# relay.net
KiCad netlist of a schematic drawn in Altium Designer
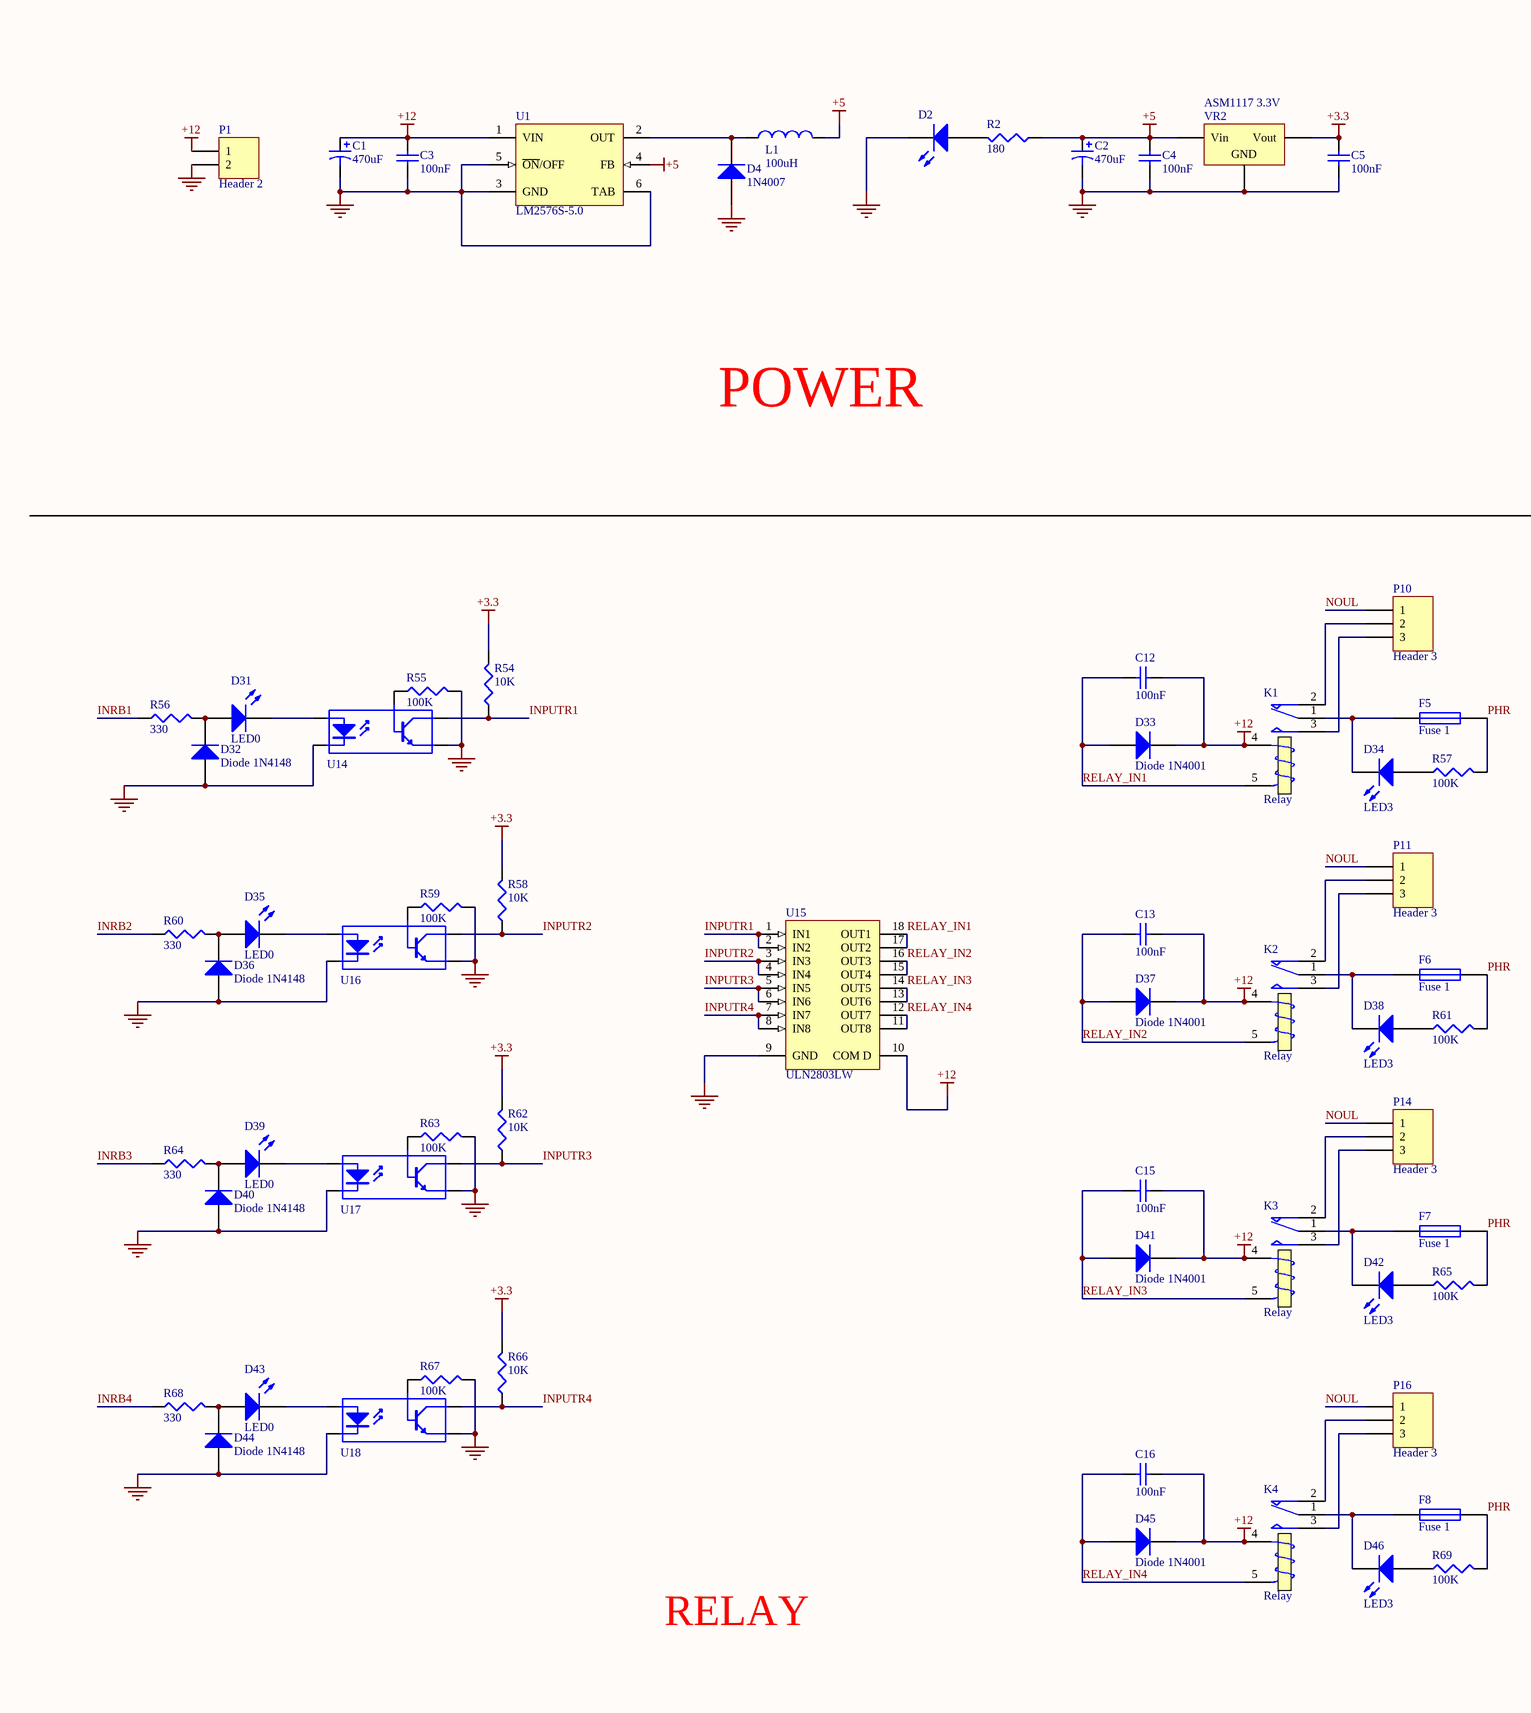
[diagram p0: relay.SchDoc, left]
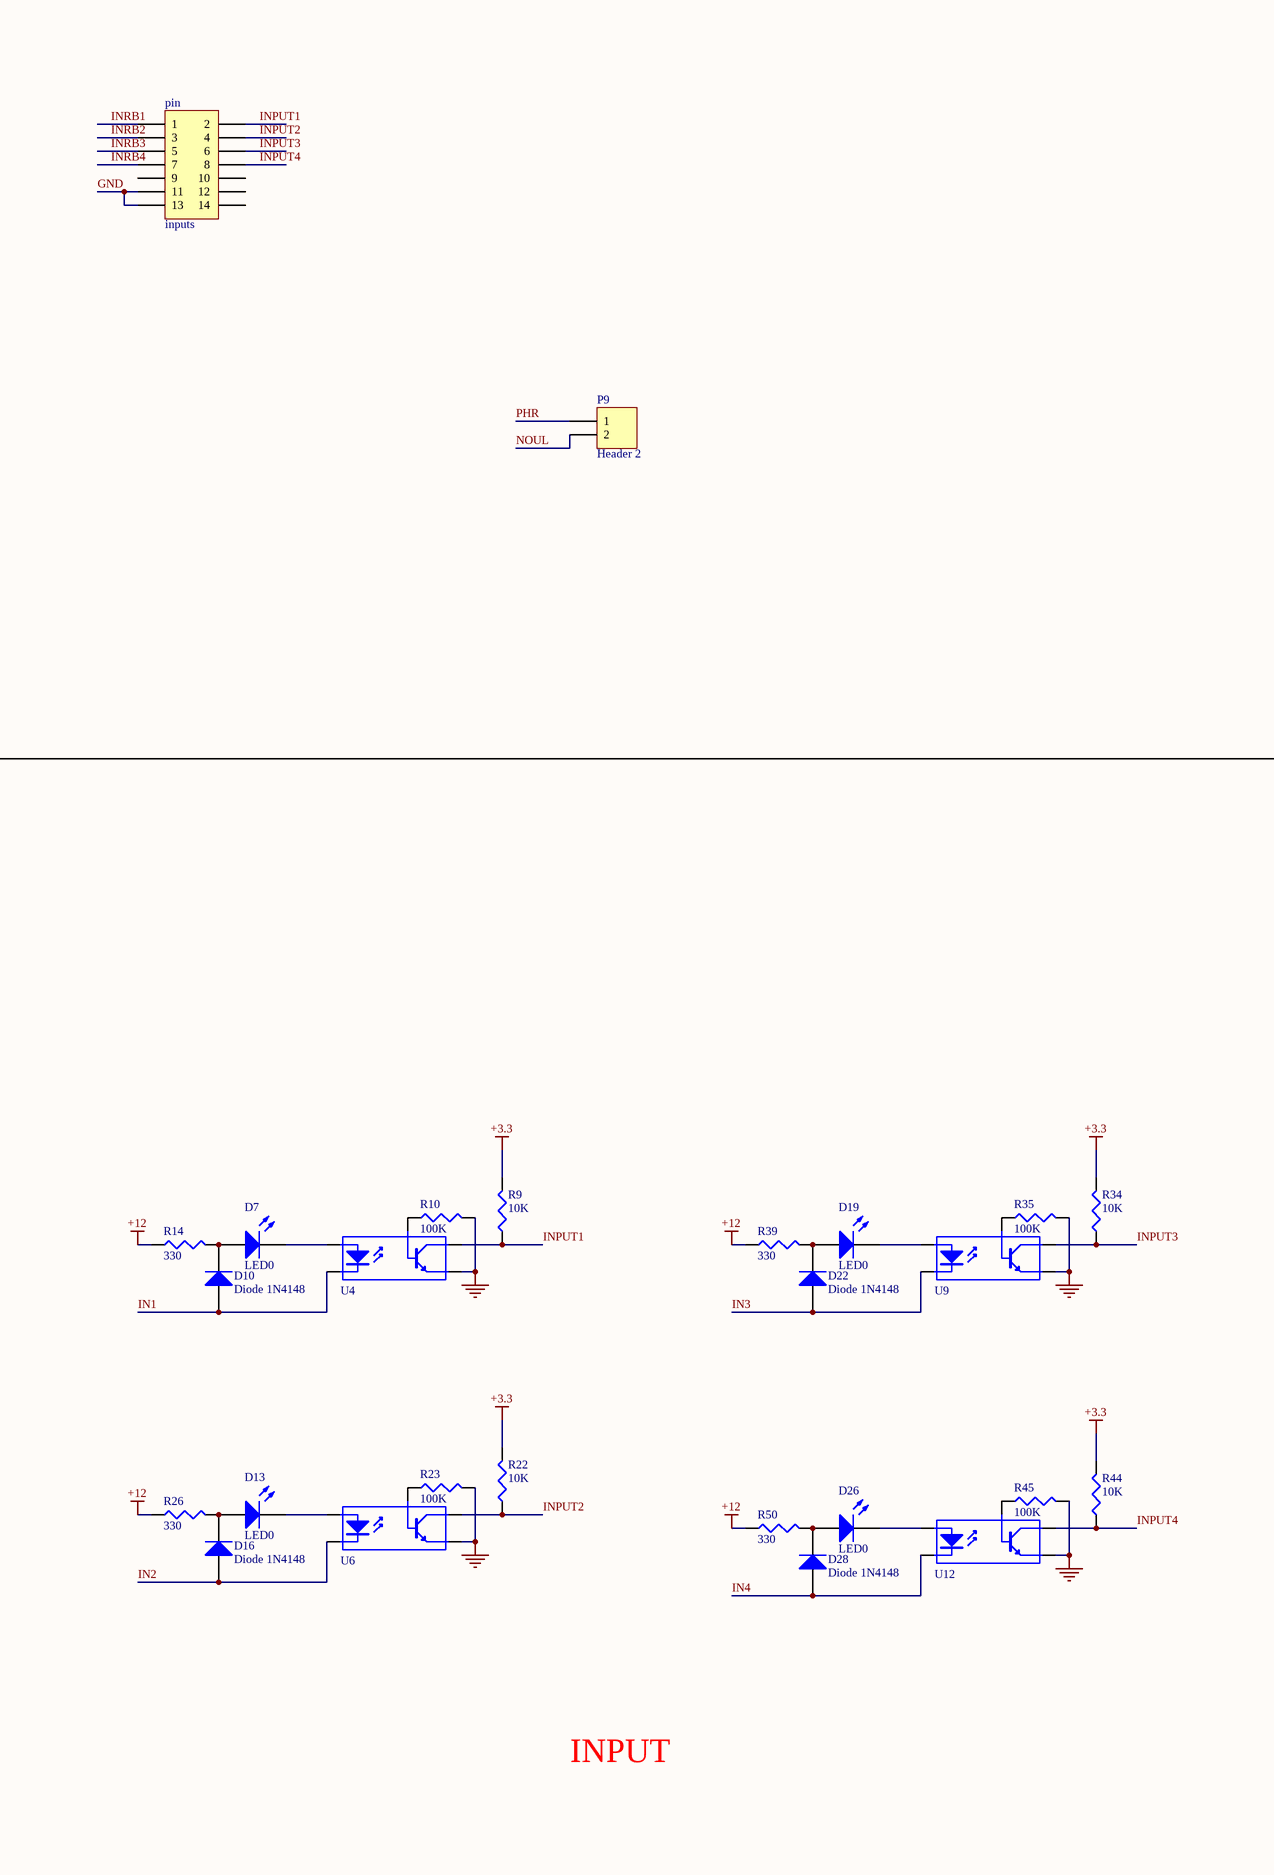
[diagram p1: relay.SchDoc, right]

(export (version "E")
  (design (tool "Eeschema 10.0.6"))
  (components
    (comp (ref "C1")
      (value "470uF")
      (footprint "CAP470")
      (description "Polarized Capacitor (Radial)")
      (fields (field (name "PUBLISHER") "Altium Limited"))
      (libsource (lib "*") (part "Cap Pol1"))
    )
    (comp (ref "C2")
      (value "470uF")
      (footprint "CAP470")
      (description "Polarized Capacitor (Radial)")
      (fields (field (name "PUBLISHER") "Altium Limited"))
      (libsource (lib "*") (part "Cap Pol1"))
    )
    (comp (ref "C3")
      (value "100nF")
      (footprint "1206")
      (description "Capacitor (Semiconductor SIM Model)")
      (fields (field (name "PUBLISHER") "Altium Limited"))
      (libsource (lib "*") (part "Cap Semi"))
    )
    (comp (ref "C4")
      (value "100nF")
      (footprint "1206")
      (description "Capacitor (Semiconductor SIM Model)")
      (fields (field (name "PUBLISHER") "Altium Limited"))
      (libsource (lib "*") (part "Cap Semi"))
    )
    (comp (ref "C5")
      (value "100nF")
      (footprint "1206")
      (description "Capacitor (Semiconductor SIM Model)")
      (fields (field (name "PUBLISHER") "Altium Limited"))
      (libsource (lib "*") (part "Cap Semi"))
    )
    (comp (ref "C12")
      (value "100nF")
      (footprint "1206")
      (description "Capacitor (Semiconductor SIM Model)")
      (fields (field (name "PUBLISHER") "Altium Limited"))
      (libsource (lib "*") (part "Cap Semi"))
    )
    (comp (ref "C13")
      (value "100nF")
      (footprint "1206")
      (description "Capacitor (Semiconductor SIM Model)")
      (fields (field (name "PUBLISHER") "Altium Limited"))
      (libsource (lib "*") (part "Cap Semi"))
    )
    (comp (ref "C15")
      (value "100nF")
      (footprint "1206")
      (description "Capacitor (Semiconductor SIM Model)")
      (fields (field (name "PUBLISHER") "Altium Limited"))
      (libsource (lib "*") (part "Cap Semi"))
    )
    (comp (ref "C16")
      (value "100nF")
      (footprint "1206")
      (description "Capacitor (Semiconductor SIM Model)")
      (fields (field (name "PUBLISHER") "Altium Limited"))
      (libsource (lib "*") (part "Cap Semi"))
    )
    (comp (ref "D2")
      (value "LED RED")
      (footprint "LED-1206")
      (description "Typical INFRARED GaAs LED")
      (fields (field (name "PUBLISHER") "Altium Limited"))
      (libsource (lib "*") (part "LED0"))
    )
    (comp (ref "D4")
      (value "1N4007")
      (footprint "1N4007")
      (description "1 Amp General Purpose Rectifier")
      (fields (field (name "PUBLISHER") "Altium Limited"))
      (libsource (lib "*") (part "Diode 1N4007"))
    )
    (comp (ref "D7")
      (value "LED0")
      (footprint "LED-1206")
      (description "Typical INFRARED GaAs LED")
      (fields (field (name "PUBLISHER") "Altium Limited"))
      (libsource (lib "*") (part "LED0"))
    )
    (comp (ref "D10")
      (value "Diode 1N4148")
      (footprint "Diode")
      (description "High Conductance Fast Diode")
      (fields (field (name "PUBLISHER") "Altium Limited"))
      (libsource (lib "*") (part "Diode 1N4148"))
    )
    (comp (ref "D13")
      (value "LED0")
      (footprint "LED-1206")
      (description "Typical INFRARED GaAs LED")
      (fields (field (name "PUBLISHER") "Altium Limited"))
      (libsource (lib "*") (part "LED0"))
    )
    (comp (ref "D16")
      (value "Diode 1N4148")
      (footprint "Diode")
      (description "High Conductance Fast Diode")
      (fields (field (name "PUBLISHER") "Altium Limited"))
      (libsource (lib "*") (part "Diode 1N4148"))
    )
    (comp (ref "D19")
      (value "LED0")
      (footprint "LED-1206")
      (description "Typical INFRARED GaAs LED")
      (fields (field (name "PUBLISHER") "Altium Limited"))
      (libsource (lib "*") (part "LED0"))
    )
    (comp (ref "D22")
      (value "Diode 1N4148")
      (footprint "Diode")
      (description "High Conductance Fast Diode")
      (fields (field (name "PUBLISHER") "Altium Limited"))
      (libsource (lib "*") (part "Diode 1N4148"))
    )
    (comp (ref "D26")
      (value "LED0")
      (footprint "LED-1206")
      (description "Typical INFRARED GaAs LED")
      (fields (field (name "PUBLISHER") "Altium Limited"))
      (libsource (lib "*") (part "LED0"))
    )
    (comp (ref "D28")
      (value "Diode 1N4148")
      (footprint "Diode")
      (description "High Conductance Fast Diode")
      (fields (field (name "PUBLISHER") "Altium Limited"))
      (libsource (lib "*") (part "Diode 1N4148"))
    )
    (comp (ref "D31")
      (value "LED0")
      (footprint "LED-1206")
      (description "Typical INFRARED GaAs LED")
      (fields (field (name "PUBLISHER") "Altium Limited"))
      (libsource (lib "*") (part "LED0"))
    )
    (comp (ref "D32")
      (value "Diode 1N4148")
      (footprint "Diode")
      (description "High Conductance Fast Diode")
      (fields (field (name "PUBLISHER") "Altium Limited"))
      (libsource (lib "*") (part "Diode 1N4148"))
    )
    (comp (ref "D33")
      (value "Diode 1N4001")
      (footprint "1N4007")
      (description "1 Amp General Purpose Rectifier")
      (fields (field (name "PUBLISHER") "Altium Limited"))
      (libsource (lib "*") (part "Diode 1N4001"))
    )
    (comp (ref "D34")
      (value "LED3")
      (footprint "LED-1206")
      (description "Typical BLUE SiC LED")
      (fields (field (name "PUBLISHER") "Altium Limited"))
      (libsource (lib "*") (part "LED3"))
    )
    (comp (ref "D35")
      (value "LED0")
      (footprint "LED-1206")
      (description "Typical INFRARED GaAs LED")
      (fields (field (name "PUBLISHER") "Altium Limited"))
      (libsource (lib "*") (part "LED0"))
    )
    (comp (ref "D36")
      (value "Diode 1N4148")
      (footprint "Diode")
      (description "High Conductance Fast Diode")
      (fields (field (name "PUBLISHER") "Altium Limited"))
      (libsource (lib "*") (part "Diode 1N4148"))
    )
    (comp (ref "D37")
      (value "Diode 1N4001")
      (footprint "1N4007")
      (description "1 Amp General Purpose Rectifier")
      (fields (field (name "PUBLISHER") "Altium Limited"))
      (libsource (lib "*") (part "Diode 1N4001"))
    )
    (comp (ref "D38")
      (value "LED3")
      (footprint "LED-1206")
      (description "Typical BLUE SiC LED")
      (fields (field (name "PUBLISHER") "Altium Limited"))
      (libsource (lib "*") (part "LED3"))
    )
    (comp (ref "D39")
      (value "LED0")
      (footprint "LED-1206")
      (description "Typical INFRARED GaAs LED")
      (fields (field (name "PUBLISHER") "Altium Limited"))
      (libsource (lib "*") (part "LED0"))
    )
    (comp (ref "D40")
      (value "Diode 1N4148")
      (footprint "Diode")
      (description "High Conductance Fast Diode")
      (fields (field (name "PUBLISHER") "Altium Limited"))
      (libsource (lib "*") (part "Diode 1N4148"))
    )
    (comp (ref "D41")
      (value "Diode 1N4001")
      (footprint "1N4007")
      (description "1 Amp General Purpose Rectifier")
      (fields (field (name "PUBLISHER") "Altium Limited"))
      (libsource (lib "*") (part "Diode 1N4001"))
    )
    (comp (ref "D42")
      (value "LED3")
      (footprint "LED-1206")
      (description "Typical BLUE SiC LED")
      (fields (field (name "PUBLISHER") "Altium Limited"))
      (libsource (lib "*") (part "LED3"))
    )
    (comp (ref "D43")
      (value "LED0")
      (footprint "LED-1206")
      (description "Typical INFRARED GaAs LED")
      (fields (field (name "PUBLISHER") "Altium Limited"))
      (libsource (lib "*") (part "LED0"))
    )
    (comp (ref "D44")
      (value "Diode 1N4148")
      (footprint "Diode")
      (description "High Conductance Fast Diode")
      (fields (field (name "PUBLISHER") "Altium Limited"))
      (libsource (lib "*") (part "Diode 1N4148"))
    )
    (comp (ref "D45")
      (value "Diode 1N4001")
      (footprint "1N4007")
      (description "1 Amp General Purpose Rectifier")
      (fields (field (name "PUBLISHER") "Altium Limited"))
      (libsource (lib "*") (part "Diode 1N4001"))
    )
    (comp (ref "D46")
      (value "LED3")
      (footprint "LED-1206")
      (description "Typical BLUE SiC LED")
      (fields (field (name "PUBLISHER") "Altium Limited"))
      (libsource (lib "*") (part "LED3"))
    )
    (comp (ref "F5")
      (value "Fuse 1")
      (footprint "FUSEXX")
      (description "Fuse")
      (fields (field (name "PUBLISHER") "Altium Limited"))
      (libsource (lib "*") (part "Fuse 1"))
    )
    (comp (ref "F6")
      (value "Fuse 1")
      (footprint "FUSEXX")
      (description "Fuse")
      (fields (field (name "PUBLISHER") "Altium Limited"))
      (libsource (lib "*") (part "Fuse 1"))
    )
    (comp (ref "F7")
      (value "Fuse 1")
      (footprint "FUSEXX")
      (description "Fuse")
      (fields (field (name "PUBLISHER") "Altium Limited"))
      (libsource (lib "*") (part "Fuse 1"))
    )
    (comp (ref "F8")
      (value "Fuse 1")
      (footprint "FUSEXX")
      (description "Fuse")
      (fields (field (name "PUBLISHER") "Altium Limited"))
      (libsource (lib "*") (part "Fuse 1"))
    )
    (comp (ref "K1")
      (value "Relay")
      (footprint "RELEY")
      (description "SPDT Relay")
      (fields (field (name "PUBLISHER") "Altium Limited"))
      (libsource (lib "*") (part "Relay"))
    )
    (comp (ref "K2")
      (value "Relay")
      (footprint "RELEY")
      (description "SPDT Relay")
      (fields (field (name "PUBLISHER") "Altium Limited"))
      (libsource (lib "*") (part "Relay"))
    )
    (comp (ref "K3")
      (value "Relay")
      (footprint "RELEY")
      (description "SPDT Relay")
      (fields (field (name "PUBLISHER") "Altium Limited"))
      (libsource (lib "*") (part "Relay"))
    )
    (comp (ref "K4")
      (value "Relay")
      (footprint "RELEY")
      (description "SPDT Relay")
      (fields (field (name "PUBLISHER") "Altium Limited"))
      (libsource (lib "*") (part "Relay"))
    )
    (comp (ref "L1") (value "100uH") (footprint "L-.2/.4") (libsource (lib "*") (part "INDUCTOR")))
    (comp (ref "P1")
      (value "Header 2")
      (footprint "POWER2_NEW")
      (description "Header, 2-Pin")
      (fields (field (name "PUBLISHER") "Altium Limited"))
      (libsource (lib "*") (part "Header 2"))
    )
    (comp (ref "P9")
      (value "Header 2")
      (footprint "POWER2_NEW")
      (description "Header, 2-Pin")
      (fields (field (name "PUBLISHER") "Altium Limited"))
      (libsource (lib "*") (part "Header 2"))
    )
    (comp (ref "P10")
      (value "Header 3")
      (footprint "POWER3_NEW")
      (description "Header, 3-Pin")
      (fields (field (name "PUBLISHER") "Altium Limited"))
      (libsource (lib "*") (part "Header 3"))
    )
    (comp (ref "P11")
      (value "Header 3")
      (footprint "POWER3_NEW")
      (description "Header, 3-Pin")
      (fields (field (name "PUBLISHER") "Altium Limited"))
      (libsource (lib "*") (part "Header 3"))
    )
    (comp (ref "P14")
      (value "Header 3")
      (footprint "POWER3_NEW")
      (description "Header, 3-Pin")
      (fields (field (name "PUBLISHER") "Altium Limited"))
      (libsource (lib "*") (part "Header 3"))
    )
    (comp (ref "P16")
      (value "Header 3")
      (footprint "POWER3_NEW")
      (description "Header, 3-Pin")
      (fields (field (name "PUBLISHER") "Altium Limited"))
      (libsource (lib "*") (part "Header 3"))
    )
    (comp (ref "pin")
      (value "inputs")
      (footprint "HDR2X7")
      (description "Header, 7-Pin, Dual row")
      (fields (field (name "PUBLISHER") "Altium Limited"))
      (libsource (lib "Miscellaneous Connectors") (part "Header 7X2"))
    )
    (comp (ref "R2")
      (value "180")
      (footprint "1206")
      (description "Resistor")
      (fields (field (name "Comment") "180R") (field (name "PUBLISHER") "Altium Limited"))
      (libsource (lib "*") (part "Res3"))
    )
    (comp (ref "R9")
      (value "10K")
      (footprint "1206")
      (description "Resistor")
      (fields (field (name "PUBLISHER") "Altium Limited"))
      (libsource (lib "*") (part "Res3"))
    )
    (comp (ref "R10")
      (value "100K")
      (footprint "1206")
      (description "Resistor")
      (fields (field (name "PUBLISHER") "Altium Limited"))
      (libsource (lib "*") (part "Res3"))
    )
    (comp (ref "R14")
      (value "330")
      (footprint "1206")
      (description "Resistor")
      (fields (field (name "PUBLISHER") "Altium Limited"))
      (libsource (lib "*") (part "Res3"))
    )
    (comp (ref "R22")
      (value "10K")
      (footprint "1206")
      (description "Resistor")
      (fields (field (name "PUBLISHER") "Altium Limited"))
      (libsource (lib "*") (part "Res3"))
    )
    (comp (ref "R23")
      (value "100K")
      (footprint "1206")
      (description "Resistor")
      (fields (field (name "PUBLISHER") "Altium Limited"))
      (libsource (lib "*") (part "Res3"))
    )
    (comp (ref "R26")
      (value "330")
      (footprint "1206")
      (description "Resistor")
      (fields (field (name "PUBLISHER") "Altium Limited"))
      (libsource (lib "*") (part "Res3"))
    )
    (comp (ref "R34")
      (value "10K")
      (footprint "1206")
      (description "Resistor")
      (fields (field (name "PUBLISHER") "Altium Limited"))
      (libsource (lib "*") (part "Res3"))
    )
    (comp (ref "R35")
      (value "100K")
      (footprint "1206")
      (description "Resistor")
      (fields (field (name "PUBLISHER") "Altium Limited"))
      (libsource (lib "*") (part "Res3"))
    )
    (comp (ref "R39")
      (value "330")
      (footprint "1206")
      (description "Resistor")
      (fields (field (name "PUBLISHER") "Altium Limited"))
      (libsource (lib "*") (part "Res3"))
    )
    (comp (ref "R44")
      (value "10K")
      (footprint "1206")
      (description "Resistor")
      (fields (field (name "PUBLISHER") "Altium Limited"))
      (libsource (lib "*") (part "Res3"))
    )
    (comp (ref "R45")
      (value "100K")
      (footprint "1206")
      (description "Resistor")
      (fields (field (name "PUBLISHER") "Altium Limited"))
      (libsource (lib "*") (part "Res3"))
    )
    (comp (ref "R50")
      (value "330")
      (footprint "1206")
      (description "Resistor")
      (fields (field (name "PUBLISHER") "Altium Limited"))
      (libsource (lib "*") (part "Res3"))
    )
    (comp (ref "R54")
      (value "10K")
      (footprint "1206")
      (description "Resistor")
      (fields (field (name "PUBLISHER") "Altium Limited"))
      (libsource (lib "*") (part "Res3"))
    )
    (comp (ref "R55")
      (value "100K")
      (footprint "1206")
      (description "Resistor")
      (fields (field (name "PUBLISHER") "Altium Limited"))
      (libsource (lib "*") (part "Res3"))
    )
    (comp (ref "R56")
      (value "330")
      (footprint "1206")
      (description "Resistor")
      (fields (field (name "PUBLISHER") "Altium Limited"))
      (libsource (lib "*") (part "Res3"))
    )
    (comp (ref "R57")
      (value "100K")
      (footprint "1206")
      (description "Resistor")
      (fields (field (name "PUBLISHER") "Altium Limited"))
      (libsource (lib "*") (part "Res3"))
    )
    (comp (ref "R58")
      (value "10K")
      (footprint "1206")
      (description "Resistor")
      (fields (field (name "PUBLISHER") "Altium Limited"))
      (libsource (lib "*") (part "Res3"))
    )
    (comp (ref "R59")
      (value "100K")
      (footprint "1206")
      (description "Resistor")
      (fields (field (name "PUBLISHER") "Altium Limited"))
      (libsource (lib "*") (part "Res3"))
    )
    (comp (ref "R60")
      (value "330")
      (footprint "1206")
      (description "Resistor")
      (fields (field (name "PUBLISHER") "Altium Limited"))
      (libsource (lib "*") (part "Res3"))
    )
    (comp (ref "R61")
      (value "100K")
      (footprint "1206")
      (description "Resistor")
      (fields (field (name "PUBLISHER") "Altium Limited"))
      (libsource (lib "*") (part "Res3"))
    )
    (comp (ref "R62")
      (value "10K")
      (footprint "1206")
      (description "Resistor")
      (fields (field (name "PUBLISHER") "Altium Limited"))
      (libsource (lib "*") (part "Res3"))
    )
    (comp (ref "R63")
      (value "100K")
      (footprint "1206")
      (description "Resistor")
      (fields (field (name "PUBLISHER") "Altium Limited"))
      (libsource (lib "*") (part "Res3"))
    )
    (comp (ref "R64")
      (value "330")
      (footprint "1206")
      (description "Resistor")
      (fields (field (name "PUBLISHER") "Altium Limited"))
      (libsource (lib "*") (part "Res3"))
    )
    (comp (ref "R65")
      (value "100K")
      (footprint "1206")
      (description "Resistor")
      (fields (field (name "PUBLISHER") "Altium Limited"))
      (libsource (lib "*") (part "Res3"))
    )
    (comp (ref "R66")
      (value "10K")
      (footprint "1206")
      (description "Resistor")
      (fields (field (name "PUBLISHER") "Altium Limited"))
      (libsource (lib "*") (part "Res3"))
    )
    (comp (ref "R67")
      (value "100K")
      (footprint "1206")
      (description "Resistor")
      (fields (field (name "PUBLISHER") "Altium Limited"))
      (libsource (lib "*") (part "Res3"))
    )
    (comp (ref "R68")
      (value "330")
      (footprint "1206")
      (description "Resistor")
      (fields (field (name "PUBLISHER") "Altium Limited"))
      (libsource (lib "*") (part "Res3"))
    )
    (comp (ref "R69")
      (value "100K")
      (footprint "1206")
      (description "Resistor")
      (fields (field (name "PUBLISHER") "Altium Limited"))
      (libsource (lib "*") (part "Res3"))
    )
    (comp (ref "U1")
      (value "LM2576S-5.0")
      (footprint "TS5B_N")
      (description "SIMPLE SWITCHER; 3A Step-Down Voltage Regulator")
      (fields
        (field (name "MANUFACTURER") "National Semiconductor")
        (field (name "DIGIKEYPARTNUMBER") "LM2576S-5.0-ND")
        (field (name "PUBLISHER") "Altium Limited")
      )
      (libsource (lib "*") (part "LM2576S-5.0"))
    )
    (comp (ref "U4")
      (value "4N29")
      (footprint "Opto")
      (description "5 Pin Mini Flat Pack Optocoupler")
      (fields (field (name "PUBLISHER") "Altium Limited"))
      (libsource (lib "*") (part "4N29"))
    )
    (comp (ref "U6")
      (value "4N29")
      (footprint "Opto")
      (description "5 Pin Mini Flat Pack Optocoupler")
      (fields (field (name "PUBLISHER") "Altium Limited"))
      (libsource (lib "*") (part "4N29"))
    )
    (comp (ref "U9")
      (value "4N29")
      (footprint "Opto")
      (description "5 Pin Mini Flat Pack Optocoupler")
      (fields (field (name "PUBLISHER") "Altium Limited"))
      (libsource (lib "*") (part "4N29"))
    )
    (comp (ref "U12")
      (value "4N29")
      (footprint "Opto")
      (description "5 Pin Mini Flat Pack Optocoupler")
      (fields (field (name "PUBLISHER") "Altium Limited"))
      (libsource (lib "*") (part "4N29"))
    )
    (comp (ref "U14")
      (value "4N29")
      (footprint "Opto")
      (description "5 Pin Mini Flat Pack Optocoupler")
      (fields (field (name "PUBLISHER") "Altium Limited"))
      (libsource (lib "*") (part "4N29"))
    )
    (comp (ref "U15")
      (value "ULN2803LW")
      (footprint "LW18_N")
      (description "High-Voltage, High-Current Darlington Array")
      (fields (field (name "PUBLISHER") "Altium Limited"))
      (libsource (lib "*") (part "ULN2803LW"))
    )
    (comp (ref "U16")
      (value "4N29")
      (footprint "Opto")
      (description "5 Pin Mini Flat Pack Optocoupler")
      (fields (field (name "PUBLISHER") "Altium Limited"))
      (libsource (lib "*") (part "4N29"))
    )
    (comp (ref "U17")
      (value "4N29")
      (footprint "Opto")
      (description "5 Pin Mini Flat Pack Optocoupler")
      (fields (field (name "PUBLISHER") "Altium Limited"))
      (libsource (lib "*") (part "4N29"))
    )
    (comp (ref "U18")
      (value "4N29")
      (footprint "Opto")
      (description "5 Pin Mini Flat Pack Optocoupler")
      (fields (field (name "PUBLISHER") "Altium Limited"))
      (libsource (lib "*") (part "4N29"))
    )
    (comp (ref "VR2")
      (value "ASM1117 3.3V")
      (footprint "Regolator")
      (description "Voltage Regulator")
      (fields (field (name "PUBLISHER") "Altium Limited"))
      (libsource (lib "*") (part "Volt Reg_1"))
    )
  )
  (nets
    (net (code "1") (name "+3.3") (class "Default")
      (node (ref "C5") (pin "2") (pinfunction "2_2") (pintype "passive"))
      (node (ref "R22") (pin "2") (pinfunction "2_2") (pintype "passive"))
      (node (ref "R34") (pin "2") (pinfunction "2_2") (pintype "passive"))
      (node (ref "R44") (pin "2") (pinfunction "2_2") (pintype "passive"))
      (node (ref "R54") (pin "2") (pinfunction "2_2") (pintype "passive"))
      (node (ref "R58") (pin "2") (pinfunction "2_2") (pintype "passive"))
      (node (ref "R62") (pin "2") (pinfunction "2_2") (pintype "passive"))
      (node (ref "R66") (pin "2") (pinfunction "2_2") (pintype "passive"))
      (node (ref "R9") (pin "2") (pinfunction "2_2") (pintype "passive"))
      (node (ref "VR2") (pin "4") (pinfunction "Vout_4") (pintype "passive"))
    )
    (net (code "2") (name "+5") (class "Default")
      (node (ref "C2") (pin "1") (pinfunction "1_1") (pintype "passive"))
      (node (ref "C4") (pin "2") (pinfunction "2_2") (pintype "passive"))
      (node (ref "L1") (pin "2") (pinfunction "2_2") (pintype "passive"))
      (node (ref "R2") (pin "1") (pinfunction "1_1") (pintype "passive"))
      (node (ref "U1") (pin "4") (pinfunction "FB_4") (pintype "input"))
      (node (ref "VR2") (pin "3") (pinfunction "Vin_3") (pintype "passive"))
    )
    (net (code "3") (name "+12") (class "Default")
      (node (ref "C1") (pin "1") (pinfunction "1_1") (pintype "passive"))
      (node (ref "C12") (pin "2") (pinfunction "2_2") (pintype "passive"))
      (node (ref "C13") (pin "2") (pinfunction "2_2") (pintype "passive"))
      (node (ref "C15") (pin "2") (pinfunction "2_2") (pintype "passive"))
      (node (ref "C16") (pin "2") (pinfunction "2_2") (pintype "passive"))
      (node (ref "C3") (pin "2") (pinfunction "2_2") (pintype "passive"))
      (node (ref "D33") (pin "2") (pinfunction "K_2") (pintype "passive"))
      (node (ref "D37") (pin "2") (pinfunction "K_2") (pintype "passive"))
      (node (ref "D41") (pin "2") (pinfunction "K_2") (pintype "passive"))
      (node (ref "D45") (pin "2") (pinfunction "K_2") (pintype "passive"))
      (node (ref "K1") (pin "4") (pinfunction "T1_4") (pintype "passive"))
      (node (ref "K2") (pin "4") (pinfunction "T1_4") (pintype "passive"))
      (node (ref "K3") (pin "4") (pinfunction "T1_4") (pintype "passive"))
      (node (ref "K4") (pin "4") (pinfunction "T1_4") (pintype "passive"))
      (node (ref "P1") (pin "1") (pinfunction "1_1") (pintype "passive"))
      (node (ref "R14") (pin "1") (pinfunction "1_1") (pintype "passive"))
      (node (ref "R26") (pin "1") (pinfunction "1_1") (pintype "passive"))
      (node (ref "R39") (pin "1") (pinfunction "1_1") (pintype "passive"))
      (node (ref "R50") (pin "1") (pinfunction "1_1") (pintype "passive"))
      (node (ref "U1") (pin "1") (pinfunction "VIN_1") (pintype "power_in"))
      (node (ref "U15") (pin "10") (pinfunction "COM_D_10") (pintype "passive"))
    )
    (net (code "4") (name "/IN1") (class "Default")
      (node (ref "D10") (pin "1") (pinfunction "A_1") (pintype "passive"))
      (node (ref "U4") (pin "3") (pinfunction "K_3") (pintype "passive"))
    )
    (net (code "5") (name "/IN2") (class "Default")
      (node (ref "D16") (pin "1") (pinfunction "A_1") (pintype "passive"))
      (node (ref "U6") (pin "3") (pinfunction "K_3") (pintype "passive"))
    )
    (net (code "6") (name "/IN3") (class "Default")
      (node (ref "D22") (pin "1") (pinfunction "A_1") (pintype "passive"))
      (node (ref "U9") (pin "3") (pinfunction "K_3") (pintype "passive"))
    )
    (net (code "7") (name "/IN4") (class "Default")
      (node (ref "D28") (pin "1") (pinfunction "A_1") (pintype "passive"))
      (node (ref "U12") (pin "3") (pinfunction "K_3") (pintype "passive"))
    )
    (net (code "8") (name "/INPUT1") (class "Default")
      (node (ref "R9") (pin "1") (pinfunction "1_1") (pintype "passive"))
      (node (ref "U4") (pin "5") (pinfunction "C_5") (pintype "passive"))
      (node (ref "pin") (pin "2") (pinfunction "2_2") (pintype "passive"))
    )
    (net (code "9") (name "/INPUT2") (class "Default")
      (node (ref "R22") (pin "1") (pinfunction "1_1") (pintype "passive"))
      (node (ref "U6") (pin "5") (pinfunction "C_5") (pintype "passive"))
      (node (ref "pin") (pin "4") (pinfunction "4_4") (pintype "passive"))
    )
    (net (code "10") (name "/INPUT3") (class "Default")
      (node (ref "R34") (pin "1") (pinfunction "1_1") (pintype "passive"))
      (node (ref "U9") (pin "5") (pinfunction "C_5") (pintype "passive"))
      (node (ref "pin") (pin "6") (pinfunction "6_6") (pintype "passive"))
    )
    (net (code "11") (name "/INPUT4") (class "Default")
      (node (ref "R44") (pin "1") (pinfunction "1_1") (pintype "passive"))
      (node (ref "U12") (pin "5") (pinfunction "C_5") (pintype "passive"))
      (node (ref "pin") (pin "8") (pinfunction "8_8") (pintype "passive"))
    )
    (net (code "12") (name "/INPUTR1") (class "Default")
      (node (ref "R54") (pin "1") (pinfunction "1_1") (pintype "passive"))
      (node (ref "U14") (pin "5") (pinfunction "C_5") (pintype "passive"))
      (node (ref "U15") (pin "1") (pinfunction "IN1_1") (pintype "input"))
      (node (ref "U15") (pin "2") (pinfunction "IN2_2") (pintype "input"))
    )
    (net (code "13") (name "/INPUTR2") (class "Default")
      (node (ref "R58") (pin "1") (pinfunction "1_1") (pintype "passive"))
      (node (ref "U15") (pin "3") (pinfunction "IN3_3") (pintype "input"))
      (node (ref "U15") (pin "4") (pinfunction "IN4_4") (pintype "input"))
      (node (ref "U16") (pin "5") (pinfunction "C_5") (pintype "passive"))
    )
    (net (code "14") (name "/INPUTR3") (class "Default")
      (node (ref "R62") (pin "1") (pinfunction "1_1") (pintype "passive"))
      (node (ref "U15") (pin "5") (pinfunction "IN5_5") (pintype "input"))
      (node (ref "U15") (pin "6") (pinfunction "IN6_6") (pintype "input"))
      (node (ref "U17") (pin "5") (pinfunction "C_5") (pintype "passive"))
    )
    (net (code "15") (name "/INPUTR4") (class "Default")
      (node (ref "R66") (pin "1") (pinfunction "1_1") (pintype "passive"))
      (node (ref "U15") (pin "7") (pinfunction "IN7_7") (pintype "input"))
      (node (ref "U15") (pin "8") (pinfunction "IN8_8") (pintype "input"))
      (node (ref "U18") (pin "5") (pinfunction "C_5") (pintype "passive"))
    )
    (net (code "16") (name "/INRB1") (class "Default")
      (node (ref "R56") (pin "1") (pinfunction "1_1") (pintype "passive"))
      (node (ref "pin") (pin "1") (pinfunction "1_1") (pintype "passive"))
    )
    (net (code "17") (name "/INRB2") (class "Default")
      (node (ref "R60") (pin "1") (pinfunction "1_1") (pintype "passive"))
      (node (ref "pin") (pin "3") (pinfunction "3_3") (pintype "passive"))
    )
    (net (code "18") (name "/INRB3") (class "Default")
      (node (ref "R64") (pin "1") (pinfunction "1_1") (pintype "passive"))
      (node (ref "pin") (pin "5") (pinfunction "5_5") (pintype "passive"))
    )
    (net (code "19") (name "/INRB4") (class "Default")
      (node (ref "R68") (pin "1") (pinfunction "1_1") (pintype "passive"))
      (node (ref "pin") (pin "7") (pinfunction "7_7") (pintype "passive"))
    )
    (net (code "20") (name "/NOUL") (class "Default")
      (node (ref "P10") (pin "1") (pinfunction "1_1") (pintype "passive"))
      (node (ref "P11") (pin "1") (pinfunction "1_1") (pintype "passive"))
      (node (ref "P14") (pin "1") (pinfunction "1_1") (pintype "passive"))
      (node (ref "P16") (pin "1") (pinfunction "1_1") (pintype "passive"))
      (node (ref "P9") (pin "2") (pinfunction "2_2") (pintype "passive"))
    )
    (net (code "21") (name "/PHR") (class "Default")
      (node (ref "F5") (pin "2") (pinfunction "2_2") (pintype "passive"))
      (node (ref "F6") (pin "2") (pinfunction "2_2") (pintype "passive"))
      (node (ref "F7") (pin "2") (pinfunction "2_2") (pintype "passive"))
      (node (ref "F8") (pin "2") (pinfunction "2_2") (pintype "passive"))
      (node (ref "P9") (pin "1") (pinfunction "1_1") (pintype "passive"))
      (node (ref "R57") (pin "2") (pinfunction "2_2") (pintype "passive"))
      (node (ref "R61") (pin "2") (pinfunction "2_2") (pintype "passive"))
      (node (ref "R65") (pin "2") (pinfunction "2_2") (pintype "passive"))
      (node (ref "R69") (pin "2") (pinfunction "2_2") (pintype "passive"))
    )
    (net (code "22") (name "/RELAY_IN1") (class "Default")
      (node (ref "C12") (pin "1") (pinfunction "1_1") (pintype "passive"))
      (node (ref "D33") (pin "1") (pinfunction "A_1") (pintype "passive"))
      (node (ref "K1") (pin "5") (pinfunction "T2_5") (pintype "passive"))
      (node (ref "U15") (pin "17") (pinfunction "OUT2_17") (pintype "open_collector"))
      (node (ref "U15") (pin "18") (pinfunction "OUT1_18") (pintype "open_collector"))
    )
    (net (code "23") (name "/RELAY_IN2") (class "Default")
      (node (ref "C13") (pin "1") (pinfunction "1_1") (pintype "passive"))
      (node (ref "D37") (pin "1") (pinfunction "A_1") (pintype "passive"))
      (node (ref "K2") (pin "5") (pinfunction "T2_5") (pintype "passive"))
      (node (ref "U15") (pin "15") (pinfunction "OUT4_15") (pintype "open_collector"))
      (node (ref "U15") (pin "16") (pinfunction "OUT3_16") (pintype "open_collector"))
    )
    (net (code "24") (name "/RELAY_IN3") (class "Default")
      (node (ref "C15") (pin "1") (pinfunction "1_1") (pintype "passive"))
      (node (ref "D41") (pin "1") (pinfunction "A_1") (pintype "passive"))
      (node (ref "K3") (pin "5") (pinfunction "T2_5") (pintype "passive"))
      (node (ref "U15") (pin "13") (pinfunction "OUT6_13") (pintype "open_collector"))
      (node (ref "U15") (pin "14") (pinfunction "OUT5_14") (pintype "open_collector"))
    )
    (net (code "25") (name "/RELAY_IN4") (class "Default")
      (node (ref "C16") (pin "1") (pinfunction "1_1") (pintype "passive"))
      (node (ref "D45") (pin "1") (pinfunction "A_1") (pintype "passive"))
      (node (ref "K4") (pin "5") (pinfunction "T2_5") (pintype "passive"))
      (node (ref "U15") (pin "11") (pinfunction "OUT8_11") (pintype "open_collector"))
      (node (ref "U15") (pin "12") (pinfunction "OUT7_12") (pintype "open_collector"))
    )
    (net (code "26") (name "GND") (class "Default")
      (node (ref "C1") (pin "2") (pinfunction "2_2") (pintype "passive"))
      (node (ref "C2") (pin "2") (pinfunction "2_2") (pintype "passive"))
      (node (ref "C3") (pin "1") (pinfunction "1_1") (pintype "passive"))
      (node (ref "C4") (pin "1") (pinfunction "1_1") (pintype "passive"))
      (node (ref "C5") (pin "1") (pinfunction "1_1") (pintype "passive"))
      (node (ref "D2") (pin "2") (pinfunction "K_2") (pintype "passive"))
      (node (ref "D32") (pin "1") (pinfunction "A_1") (pintype "passive"))
      (node (ref "D36") (pin "1") (pinfunction "A_1") (pintype "passive"))
      (node (ref "D4") (pin "1") (pinfunction "A_1") (pintype "passive"))
      (node (ref "D40") (pin "1") (pinfunction "A_1") (pintype "passive"))
      (node (ref "D44") (pin "1") (pinfunction "A_1") (pintype "passive"))
      (node (ref "P1") (pin "2") (pinfunction "2_2") (pintype "passive"))
      (node (ref "R10") (pin "2") (pinfunction "2_2") (pintype "passive"))
      (node (ref "R23") (pin "2") (pinfunction "2_2") (pintype "passive"))
      (node (ref "R35") (pin "2") (pinfunction "2_2") (pintype "passive"))
      (node (ref "R45") (pin "2") (pinfunction "2_2") (pintype "passive"))
      (node (ref "R55") (pin "2") (pinfunction "2_2") (pintype "passive"))
      (node (ref "R59") (pin "2") (pinfunction "2_2") (pintype "passive"))
      (node (ref "R63") (pin "2") (pinfunction "2_2") (pintype "passive"))
      (node (ref "R67") (pin "2") (pinfunction "2_2") (pintype "passive"))
      (node (ref "U1") (pin "3") (pinfunction "GND_3") (pintype "power_in"))
      (node (ref "U1") (pin "5") (pinfunction "~{ON}/OFF_5") (pintype "input"))
      (node (ref "U1") (pin "6") (pinfunction "TAB_6") (pintype "power_in"))
      (node (ref "U12") (pin "4") (pinfunction "E_4") (pintype "passive"))
      (node (ref "U14") (pin "3") (pinfunction "K_3") (pintype "passive"))
      (node (ref "U14") (pin "4") (pinfunction "E_4") (pintype "passive"))
      (node (ref "U15") (pin "9") (pinfunction "GND_9") (pintype "power_in"))
      (node (ref "U16") (pin "3") (pinfunction "K_3") (pintype "passive"))
      (node (ref "U16") (pin "4") (pinfunction "E_4") (pintype "passive"))
      (node (ref "U17") (pin "3") (pinfunction "K_3") (pintype "passive"))
      (node (ref "U17") (pin "4") (pinfunction "E_4") (pintype "passive"))
      (node (ref "U18") (pin "3") (pinfunction "K_3") (pintype "passive"))
      (node (ref "U18") (pin "4") (pinfunction "E_4") (pintype "passive"))
      (node (ref "U4") (pin "4") (pinfunction "E_4") (pintype "passive"))
      (node (ref "U6") (pin "4") (pinfunction "E_4") (pintype "passive"))
      (node (ref "U9") (pin "4") (pinfunction "E_4") (pintype "passive"))
      (node (ref "VR2") (pin "1") (pinfunction "GND_1") (pintype "passive"))
      (node (ref "pin") (pin "11") (pinfunction "11_11") (pintype "passive"))
      (node (ref "pin") (pin "13") (pinfunction "13_13") (pintype "passive"))
    )
    (net (code "27") (name "Net-(D2-A)") (class "Default")
      (node (ref "D2") (pin "1") (pinfunction "A_1") (pintype "passive"))
      (node (ref "R2") (pin "2") (pinfunction "2_2") (pintype "passive"))
    )
    (net (code "28") (name "Net-(D4-K)") (class "Default")
      (node (ref "D4") (pin "2") (pinfunction "K_2") (pintype "passive"))
      (node (ref "L1") (pin "1") (pinfunction "1_1") (pintype "passive"))
      (node (ref "U1") (pin "2") (pinfunction "OUT_2") (pintype "power_in"))
    )
    (net (code "29") (name "Net-(D7-K)") (class "Default")
      (node (ref "D7") (pin "2") (pinfunction "K_2") (pintype "passive"))
      (node (ref "U4") (pin "1") (pinfunction "A_1") (pintype "passive"))
    )
    (net (code "30") (name "Net-(D10-K)") (class "Default")
      (node (ref "D10") (pin "2") (pinfunction "K_2") (pintype "passive"))
      (node (ref "D7") (pin "1") (pinfunction "A_1") (pintype "passive"))
      (node (ref "R14") (pin "2") (pinfunction "2_2") (pintype "passive"))
    )
    (net (code "31") (name "Net-(D13-A)") (class "Default")
      (node (ref "D13") (pin "1") (pinfunction "A_1") (pintype "passive"))
      (node (ref "D16") (pin "2") (pinfunction "K_2") (pintype "passive"))
      (node (ref "R26") (pin "2") (pinfunction "2_2") (pintype "passive"))
    )
    (net (code "32") (name "Net-(D13-K)") (class "Default")
      (node (ref "D13") (pin "2") (pinfunction "K_2") (pintype "passive"))
      (node (ref "U6") (pin "1") (pinfunction "A_1") (pintype "passive"))
    )
    (net (code "33") (name "Net-(D19-A)") (class "Default")
      (node (ref "D19") (pin "1") (pinfunction "A_1") (pintype "passive"))
      (node (ref "D22") (pin "2") (pinfunction "K_2") (pintype "passive"))
      (node (ref "R39") (pin "2") (pinfunction "2_2") (pintype "passive"))
    )
    (net (code "34") (name "Net-(D19-K)") (class "Default")
      (node (ref "D19") (pin "2") (pinfunction "K_2") (pintype "passive"))
      (node (ref "U9") (pin "1") (pinfunction "A_1") (pintype "passive"))
    )
    (net (code "35") (name "Net-(D26-A)") (class "Default")
      (node (ref "D26") (pin "1") (pinfunction "A_1") (pintype "passive"))
      (node (ref "D28") (pin "2") (pinfunction "K_2") (pintype "passive"))
      (node (ref "R50") (pin "2") (pinfunction "2_2") (pintype "passive"))
    )
    (net (code "36") (name "Net-(D26-K)") (class "Default")
      (node (ref "D26") (pin "2") (pinfunction "K_2") (pintype "passive"))
      (node (ref "U12") (pin "1") (pinfunction "A_1") (pintype "passive"))
    )
    (net (code "37") (name "Net-(D31-A)") (class "Default")
      (node (ref "D31") (pin "1") (pinfunction "A_1") (pintype "passive"))
      (node (ref "D32") (pin "2") (pinfunction "K_2") (pintype "passive"))
      (node (ref "R56") (pin "2") (pinfunction "2_2") (pintype "passive"))
    )
    (net (code "38") (name "Net-(D31-K)") (class "Default")
      (node (ref "D31") (pin "2") (pinfunction "K_2") (pintype "passive"))
      (node (ref "U14") (pin "1") (pinfunction "A_1") (pintype "passive"))
    )
    (net (code "39") (name "Net-(D34-A)") (class "Default")
      (node (ref "D34") (pin "1") (pinfunction "A_1") (pintype "passive"))
      (node (ref "R57") (pin "1") (pinfunction "1_1") (pintype "passive"))
    )
    (net (code "40") (name "Net-(D34-K)") (class "Default")
      (node (ref "D34") (pin "2") (pinfunction "K_2") (pintype "passive"))
      (node (ref "F5") (pin "1") (pinfunction "1_1") (pintype "passive"))
      (node (ref "K1") (pin "1") (pinfunction "COM_1") (pintype "passive"))
    )
    (net (code "41") (name "Net-(D35-A)") (class "Default")
      (node (ref "D35") (pin "1") (pinfunction "A_1") (pintype "passive"))
      (node (ref "D36") (pin "2") (pinfunction "K_2") (pintype "passive"))
      (node (ref "R60") (pin "2") (pinfunction "2_2") (pintype "passive"))
    )
    (net (code "42") (name "Net-(D35-K)") (class "Default")
      (node (ref "D35") (pin "2") (pinfunction "K_2") (pintype "passive"))
      (node (ref "U16") (pin "1") (pinfunction "A_1") (pintype "passive"))
    )
    (net (code "43") (name "Net-(D38-A)") (class "Default")
      (node (ref "D38") (pin "1") (pinfunction "A_1") (pintype "passive"))
      (node (ref "R61") (pin "1") (pinfunction "1_1") (pintype "passive"))
    )
    (net (code "44") (name "Net-(D38-K)") (class "Default")
      (node (ref "D38") (pin "2") (pinfunction "K_2") (pintype "passive"))
      (node (ref "F6") (pin "1") (pinfunction "1_1") (pintype "passive"))
      (node (ref "K2") (pin "1") (pinfunction "COM_1") (pintype "passive"))
    )
    (net (code "45") (name "Net-(D39-A)") (class "Default")
      (node (ref "D39") (pin "1") (pinfunction "A_1") (pintype "passive"))
      (node (ref "D40") (pin "2") (pinfunction "K_2") (pintype "passive"))
      (node (ref "R64") (pin "2") (pinfunction "2_2") (pintype "passive"))
    )
    (net (code "46") (name "Net-(D39-K)") (class "Default")
      (node (ref "D39") (pin "2") (pinfunction "K_2") (pintype "passive"))
      (node (ref "U17") (pin "1") (pinfunction "A_1") (pintype "passive"))
    )
    (net (code "47") (name "Net-(D42-A)") (class "Default")
      (node (ref "D42") (pin "1") (pinfunction "A_1") (pintype "passive"))
      (node (ref "R65") (pin "1") (pinfunction "1_1") (pintype "passive"))
    )
    (net (code "48") (name "Net-(D42-K)") (class "Default")
      (node (ref "D42") (pin "2") (pinfunction "K_2") (pintype "passive"))
      (node (ref "F7") (pin "1") (pinfunction "1_1") (pintype "passive"))
      (node (ref "K3") (pin "1") (pinfunction "COM_1") (pintype "passive"))
    )
    (net (code "49") (name "Net-(D43-A)") (class "Default")
      (node (ref "D43") (pin "1") (pinfunction "A_1") (pintype "passive"))
      (node (ref "D44") (pin "2") (pinfunction "K_2") (pintype "passive"))
      (node (ref "R68") (pin "2") (pinfunction "2_2") (pintype "passive"))
    )
    (net (code "50") (name "Net-(D43-K)") (class "Default")
      (node (ref "D43") (pin "2") (pinfunction "K_2") (pintype "passive"))
      (node (ref "U18") (pin "1") (pinfunction "A_1") (pintype "passive"))
    )
    (net (code "51") (name "Net-(D46-A)") (class "Default")
      (node (ref "D46") (pin "1") (pinfunction "A_1") (pintype "passive"))
      (node (ref "R69") (pin "1") (pinfunction "1_1") (pintype "passive"))
    )
    (net (code "52") (name "Net-(D46-K)") (class "Default")
      (node (ref "D46") (pin "2") (pinfunction "K_2") (pintype "passive"))
      (node (ref "F8") (pin "1") (pinfunction "1_1") (pintype "passive"))
      (node (ref "K4") (pin "1") (pinfunction "COM_1") (pintype "passive"))
    )
    (net (code "53") (name "Net-(K1-NC)") (class "Default")
      (node (ref "K1") (pin "2") (pinfunction "NC_2") (pintype "passive"))
      (node (ref "P10") (pin "2") (pinfunction "2_2") (pintype "passive"))
    )
    (net (code "54") (name "Net-(K1-NO)") (class "Default")
      (node (ref "K1") (pin "3") (pinfunction "NO_3") (pintype "passive"))
      (node (ref "P10") (pin "3") (pinfunction "3_3") (pintype "passive"))
    )
    (net (code "55") (name "Net-(K2-NC)") (class "Default")
      (node (ref "K2") (pin "2") (pinfunction "NC_2") (pintype "passive"))
      (node (ref "P11") (pin "2") (pinfunction "2_2") (pintype "passive"))
    )
    (net (code "56") (name "Net-(K2-NO)") (class "Default")
      (node (ref "K2") (pin "3") (pinfunction "NO_3") (pintype "passive"))
      (node (ref "P11") (pin "3") (pinfunction "3_3") (pintype "passive"))
    )
    (net (code "57") (name "Net-(K3-NC)") (class "Default")
      (node (ref "K3") (pin "2") (pinfunction "NC_2") (pintype "passive"))
      (node (ref "P14") (pin "2") (pinfunction "2_2") (pintype "passive"))
    )
    (net (code "58") (name "Net-(K3-NO)") (class "Default")
      (node (ref "K3") (pin "3") (pinfunction "NO_3") (pintype "passive"))
      (node (ref "P14") (pin "3") (pinfunction "3_3") (pintype "passive"))
    )
    (net (code "59") (name "Net-(K4-NC)") (class "Default")
      (node (ref "K4") (pin "2") (pinfunction "NC_2") (pintype "passive"))
      (node (ref "P16") (pin "2") (pinfunction "2_2") (pintype "passive"))
    )
    (net (code "60") (name "Net-(K4-NO)") (class "Default")
      (node (ref "K4") (pin "3") (pinfunction "NO_3") (pintype "passive"))
      (node (ref "P16") (pin "3") (pinfunction "3_3") (pintype "passive"))
    )
    (net (code "61") (name "Net-(U4-B)") (class "Default")
      (node (ref "R10") (pin "1") (pinfunction "1_1") (pintype "passive"))
      (node (ref "U4") (pin "6") (pinfunction "B_6") (pintype "passive"))
    )
    (net (code "62") (name "Net-(U6-B)") (class "Default")
      (node (ref "R23") (pin "1") (pinfunction "1_1") (pintype "passive"))
      (node (ref "U6") (pin "6") (pinfunction "B_6") (pintype "passive"))
    )
    (net (code "63") (name "Net-(U9-B)") (class "Default")
      (node (ref "R35") (pin "1") (pinfunction "1_1") (pintype "passive"))
      (node (ref "U9") (pin "6") (pinfunction "B_6") (pintype "passive"))
    )
    (net (code "64") (name "Net-(U12-B)") (class "Default")
      (node (ref "R45") (pin "1") (pinfunction "1_1") (pintype "passive"))
      (node (ref "U12") (pin "6") (pinfunction "B_6") (pintype "passive"))
    )
    (net (code "65") (name "Net-(U14-B)") (class "Default")
      (node (ref "R55") (pin "1") (pinfunction "1_1") (pintype "passive"))
      (node (ref "U14") (pin "6") (pinfunction "B_6") (pintype "passive"))
    )
    (net (code "66") (name "Net-(U16-B)") (class "Default")
      (node (ref "R59") (pin "1") (pinfunction "1_1") (pintype "passive"))
      (node (ref "U16") (pin "6") (pinfunction "B_6") (pintype "passive"))
    )
    (net (code "67") (name "Net-(U17-B)") (class "Default")
      (node (ref "R63") (pin "1") (pinfunction "1_1") (pintype "passive"))
      (node (ref "U17") (pin "6") (pinfunction "B_6") (pintype "passive"))
    )
    (net (code "68") (name "Net-(U18-B)") (class "Default")
      (node (ref "R67") (pin "1") (pinfunction "1_1") (pintype "passive"))
      (node (ref "U18") (pin "6") (pinfunction "B_6") (pintype "passive"))
    )
    (net (code "69") (name "unconnected-(pin-Pad9)") (class "Default")
      (node (ref "pin") (pin "9") (pinfunction "9_9") (pintype "passive"))
    )
    (net (code "70") (name "unconnected-(pin-Pad10)") (class "Default")
      (node (ref "pin") (pin "10") (pinfunction "10_10") (pintype "passive"))
    )
    (net (code "71") (name "unconnected-(pin-Pad12)") (class "Default")
      (node (ref "pin") (pin "12") (pinfunction "12_12") (pintype "passive"))
    )
    (net (code "72") (name "unconnected-(pin-Pad14)") (class "Default")
      (node (ref "pin") (pin "14") (pinfunction "14_14") (pintype "passive"))
    )
  )
)
